# Electronic_Design_OpenBook_Hardware_v1.net
KiCad netlist of a schematic drawn in EAGLE
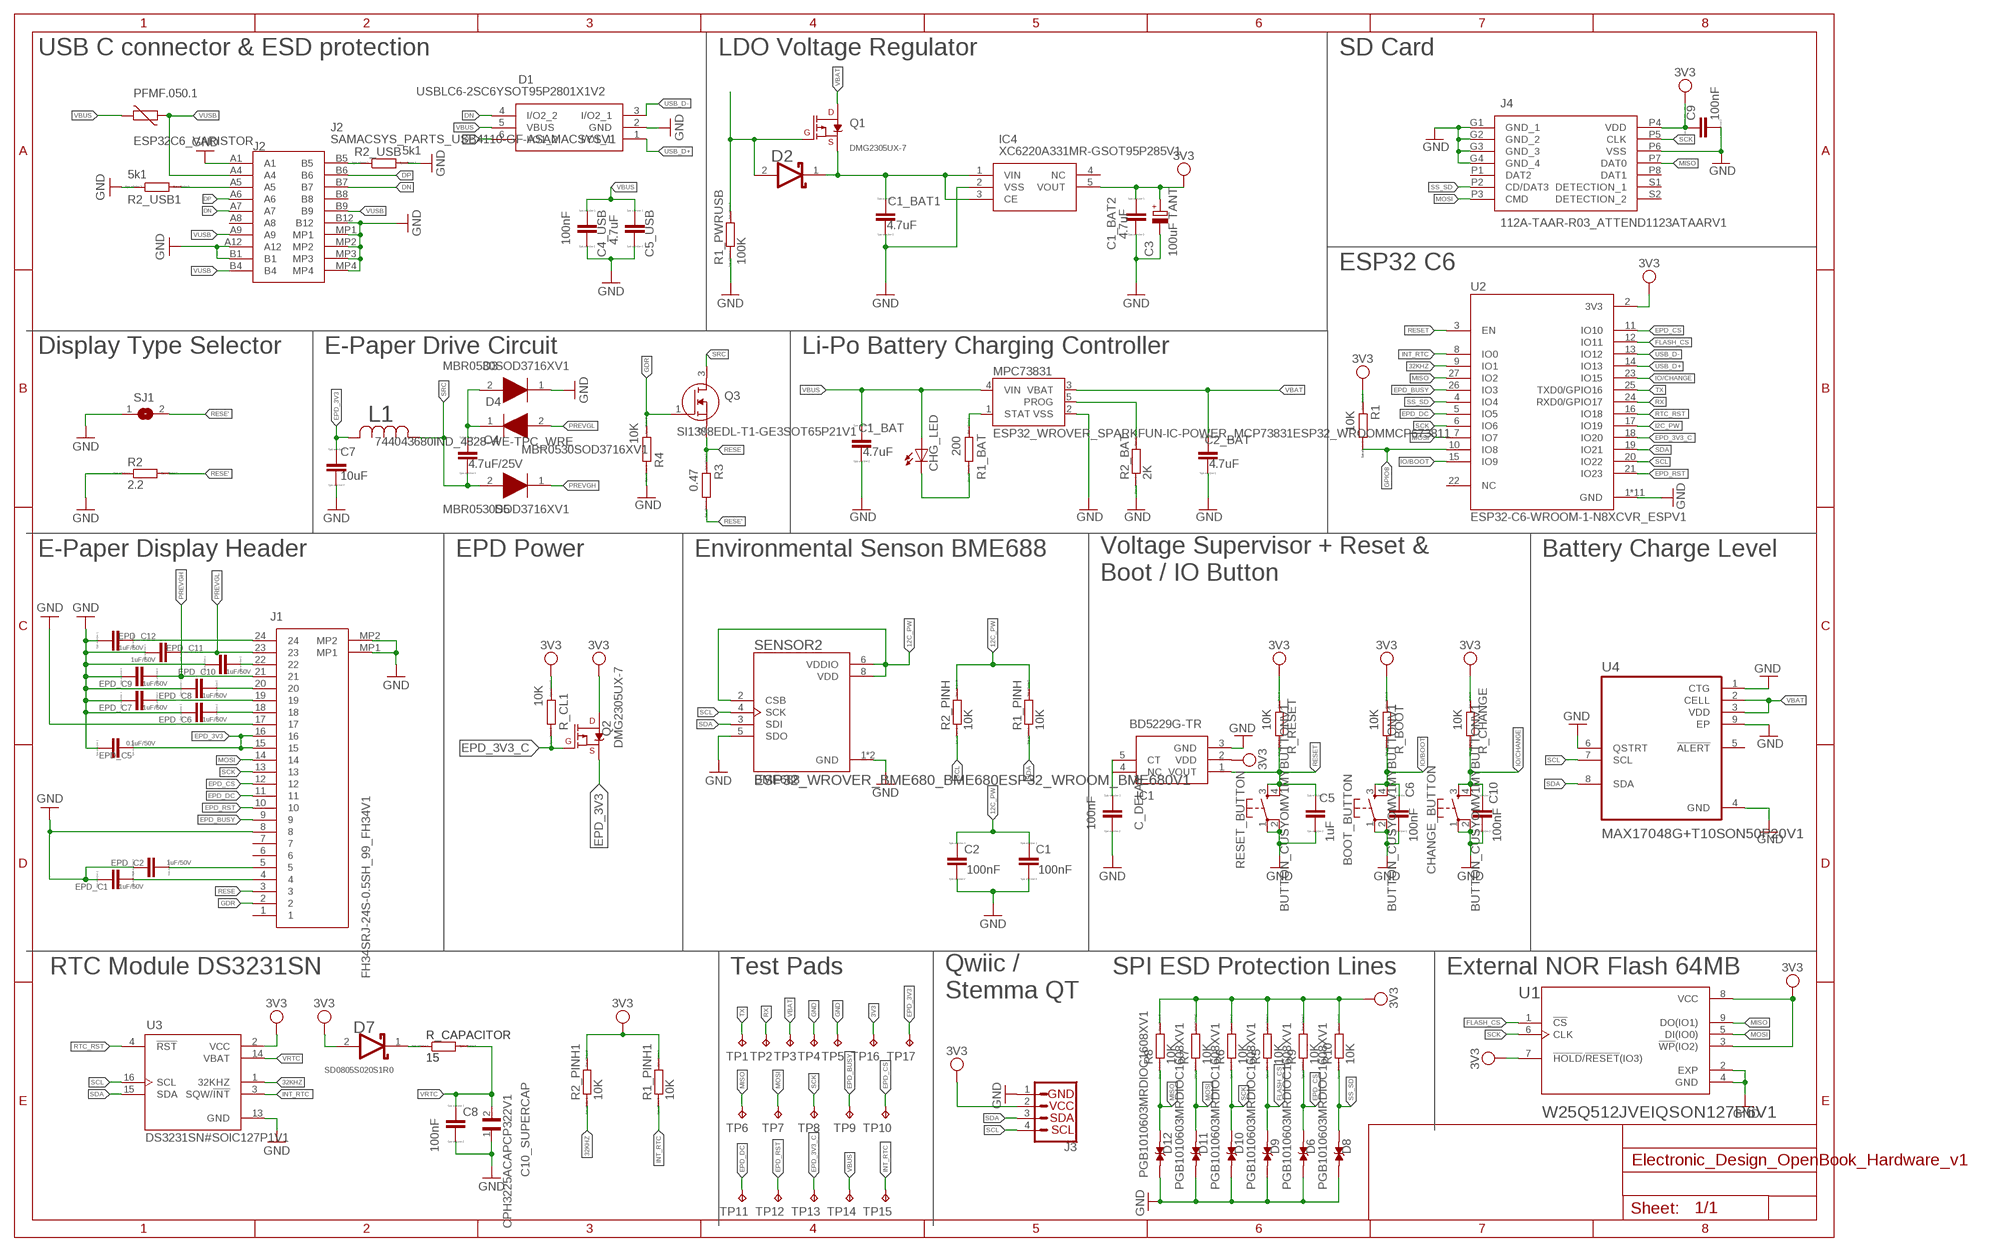
[diagram p0: schematic, sheet 1]

(export (version "E")
  (design (tool "Eeschema 10.0.6"))
  (components
    (comp (ref "BOOT_BUTTON")
      (value "BUTTON_CUSYOMV1MYBUTTONV1")
      (footprint "eagle-import:MYBUTTON")
      (libsource (lib "eagle-import") (part "BUTTON_CUSYOMV1MYBUTTONV1"))
    )
    (comp (ref "C1")
      (value "100nF")
      (footprint "eagle-import:EAGLE-LTSPICE_C0402")
      (libsource (lib "eagle-import") (part "EAGLE-LTSPICE_CC0402"))
    )
    (comp (ref "C1_BAT")
      (value "4.7uF")
      (footprint "eagle-import:ESP32_WROVER_EAGLE-LTSPICE_C0402")
      (libsource (lib "eagle-import") (part "ESP32_WROVER_EAGLE-LTSPICE_C"))
    )
    (comp (ref "C1_BAT1")
      (value "4.7uF")
      (footprint "eagle-import:ESP32_WROVER_EAGLE-LTSPICE_C0402")
      (libsource (lib "eagle-import") (part "ESP32_WROVER_EAGLE-LTSPICE_C"))
    )
    (comp (ref "C1_BAT2")
      (value "4.7uF")
      (footprint "eagle-import:ESP32_WROVER_EAGLE-LTSPICE_C0402")
      (libsource (lib "eagle-import") (part "ESP32_WROVER_EAGLE-LTSPICE_C"))
    )
    (comp (ref "C2")
      (value "100nF")
      (footprint "eagle-import:EAGLE-LTSPICE_C0402")
      (libsource (lib "eagle-import") (part "EAGLE-LTSPICE_CC0402"))
    )
    (comp (ref "C2_BAT")
      (value "4.7uF")
      (footprint "eagle-import:ESP32_WROVER_EAGLE-LTSPICE_C0402")
      (libsource (lib "eagle-import") (part "ESP32_WROVER_EAGLE-LTSPICE_C"))
    )
    (comp (ref "C3")
      (value "100uF TANT")
      (footprint "eagle-import:RCL_CT3528")
      (libsource (lib "eagle-import") (part "RCL_CPOL-EU"))
    )
    (comp (ref "C4")
      (value "4.7uF/25V")
      (footprint "eagle-import:ESP32_WROVER_EAGLE-LTSPICE_C0402")
      (libsource (lib "eagle-import") (part "ESP32_WROVER_EAGLE-LTSPICE_C"))
    )
    (comp (ref "C4_USB")
      (value "100nF")
      (footprint "eagle-import:ESP32_WROVER_EAGLE-LTSPICE_C0402")
      (libsource (lib "eagle-import") (part "ESP32_WROVER_EAGLE-LTSPICE_C"))
    )
    (comp (ref "C5")
      (value "1uF")
      (footprint "eagle-import:EAGLE-LTSPICE_C0402")
      (libsource (lib "eagle-import") (part "EAGLE-LTSPICE_CC0402"))
    )
    (comp (ref "C5_USB")
      (value "4.7uF")
      (footprint "eagle-import:ESP32_WROVER_EAGLE-LTSPICE_C0402")
      (libsource (lib "eagle-import") (part "ESP32_WROVER_EAGLE-LTSPICE_C"))
    )
    (comp (ref "C6")
      (value "100nF")
      (footprint "eagle-import:EAGLE-LTSPICE_C0402")
      (libsource (lib "eagle-import") (part "EAGLE-LTSPICE_CC0402"))
    )
    (comp (ref "C7")
      (value "10uF")
      (footprint "eagle-import:ESP32_WROVER_EAGLE-LTSPICE_C0402")
      (libsource (lib "eagle-import") (part "ESP32_WROVER_EAGLE-LTSPICE_C"))
    )
    (comp (ref "C8")
      (value "100nF")
      (footprint "eagle-import:EAGLE-LTSPICE_C0402")
      (libsource (lib "eagle-import") (part "EAGLE-LTSPICE_CC0402"))
    )
    (comp (ref "C9")
      (value "100nF")
      (footprint "eagle-import:ESP32_WROVER_EAGLE-LTSPICE_C0402")
      (libsource (lib "eagle-import") (part "ESP32_WROVER_EAGLE-LTSPICE_C"))
    )
    (comp (ref "C10")
      (value "100nF")
      (footprint "eagle-import:EAGLE-LTSPICE_C0402")
      (libsource (lib "eagle-import") (part "EAGLE-LTSPICE_CC0402"))
    )
    (comp (ref "C10_SUPERCAP")
      (value "CPH3225ACAPCP322V1")
      (footprint "eagle-import:CAPCP3225X100N")
      (libsource (lib "eagle-import") (part "CPH3225ACAPCP322V1"))
    )
    (comp (ref "CHANGE_BUTTON")
      (value "BUTTON_CUSYOMV1MYBUTTONV1")
      (footprint "eagle-import:MYBUTTON")
      (libsource (lib "eagle-import") (part "BUTTON_CUSYOMV1MYBUTTONV1"))
    )
    (comp (ref "CHG_LED")
      (value "ADAFRUIT_LED")
      (footprint "eagle-import:ADAFRUIT_CHIP-LED0603")
      (libsource (lib "eagle-import") (part "ADAFRUIT_LED"))
    )
    (comp (ref "C_DELAY")
      (value "100nF")
      (footprint "eagle-import:EAGLE-LTSPICE_C0402")
      (libsource (lib "eagle-import") (part "EAGLE-LTSPICE_CC0402"))
    )
    (comp (ref "D1")
      (value "USBLC6-2SC6YSOT95P2801X1V2")
      (footprint "eagle-import:SOT95P280X145-6N")
      (libsource (lib "eagle-import") (part "USBLC6-2SC6YSOT95P2801X1V2"))
    )
    (comp (ref "D2")
      (value "ESP32_WROVER_AVX---SD0805S020S1R0_AVX_SD0805S020S1R0_0_0")
      (footprint "eagle-import:ESP32_WROVER_AVX---SD0805S020S1R0_AVX_SD0805S020S1R0_0")
      (libsource (lib "eagle-import") (part "ESP32_WROVER_AVX---SD0805S020S1R0_AVX_SD0805S020S1R0_0_0"))
    )
    (comp (ref "D3")
      (value "MBR0530SOD3716XV1")
      (footprint "eagle-import:SOD3716X135N")
      (libsource (lib "eagle-import") (part "MBR0530SOD3716XV1"))
    )
    (comp (ref "D4")
      (value "MBR0530SOD3716XV1")
      (footprint "eagle-import:SOD3716X135N")
      (libsource (lib "eagle-import") (part "MBR0530SOD3716XV1"))
    )
    (comp (ref "D5")
      (value "MBR0530SOD3716XV1")
      (footprint "eagle-import:SOD3716X135N")
      (libsource (lib "eagle-import") (part "MBR0530SOD3716XV1"))
    )
    (comp (ref "D6")
      (value "PGB1010603MRDIOC1608XV1")
      (footprint "eagle-import:DIOC1608X36N")
      (libsource (lib "eagle-import") (part "PGB1010603MRDIOC1608XV1"))
    )
    (comp (ref "D7")
      (value "ESP32_WROVER_AVX---SD0805S020S1R0_AVX_SD0805S020S1R0_0_0")
      (footprint "eagle-import:ESP32_WROVER_AVX---SD0805S020S1R0_AVX_SD0805S020S1R0_0")
      (libsource (lib "eagle-import") (part "ESP32_WROVER_AVX---SD0805S020S1R0_AVX_SD0805S020S1R0_0_0"))
    )
    (comp (ref "D8")
      (value "PGB1010603MRDIOC1608XV1")
      (footprint "eagle-import:DIOC1608X36N")
      (libsource (lib "eagle-import") (part "PGB1010603MRDIOC1608XV1"))
    )
    (comp (ref "D9")
      (value "PGB1010603MRDIOC1608XV1")
      (footprint "eagle-import:DIOC1608X36N")
      (libsource (lib "eagle-import") (part "PGB1010603MRDIOC1608XV1"))
    )
    (comp (ref "D10")
      (value "PGB1010603MRDIOC1608XV1")
      (footprint "eagle-import:DIOC1608X36N")
      (libsource (lib "eagle-import") (part "PGB1010603MRDIOC1608XV1"))
    )
    (comp (ref "D11")
      (value "PGB1010603MRDIOC1608XV1")
      (footprint "eagle-import:DIOC1608X36N")
      (libsource (lib "eagle-import") (part "PGB1010603MRDIOC1608XV1"))
    )
    (comp (ref "D12")
      (value "PGB1010603MRDIOC1608XV1")
      (footprint "eagle-import:DIOC1608X36N")
      (libsource (lib "eagle-import") (part "PGB1010603MRDIOC1608XV1"))
    )
    (comp (ref "EPD_C1")
      (value "1uF/50V")
      (footprint "eagle-import:EAGLE-LTSPICE_C0402")
      (libsource (lib "eagle-import") (part "EAGLE-LTSPICE_CC0402"))
    )
    (comp (ref "EPD_C2")
      (value "1uF/50V")
      (footprint "eagle-import:EAGLE-LTSPICE_C0402")
      (libsource (lib "eagle-import") (part "EAGLE-LTSPICE_CC0402"))
    )
    (comp (ref "EPD_C5")
      (value "0.1uF/50V")
      (footprint "eagle-import:EAGLE-LTSPICE_C0402")
      (libsource (lib "eagle-import") (part "EAGLE-LTSPICE_CC0402"))
    )
    (comp (ref "EPD_C6")
      (value "1uF/50V")
      (footprint "eagle-import:EAGLE-LTSPICE_C0402")
      (libsource (lib "eagle-import") (part "EAGLE-LTSPICE_CC0402"))
    )
    (comp (ref "EPD_C7")
      (value "1uF/50V")
      (footprint "eagle-import:EAGLE-LTSPICE_C0402")
      (libsource (lib "eagle-import") (part "EAGLE-LTSPICE_CC0402"))
    )
    (comp (ref "EPD_C8")
      (value "1uF/50V")
      (footprint "eagle-import:EAGLE-LTSPICE_C0402")
      (libsource (lib "eagle-import") (part "EAGLE-LTSPICE_CC0402"))
    )
    (comp (ref "EPD_C9")
      (value "1uF/50V")
      (footprint "eagle-import:EAGLE-LTSPICE_C0402")
      (libsource (lib "eagle-import") (part "EAGLE-LTSPICE_CC0402"))
    )
    (comp (ref "EPD_C10")
      (value "1uF/50V")
      (footprint "eagle-import:EAGLE-LTSPICE_C0402")
      (libsource (lib "eagle-import") (part "EAGLE-LTSPICE_CC0402"))
    )
    (comp (ref "EPD_C11")
      (value "1uF/50V")
      (footprint "eagle-import:EAGLE-LTSPICE_C0402")
      (libsource (lib "eagle-import") (part "EAGLE-LTSPICE_CC0402"))
    )
    (comp (ref "EPD_C12")
      (value "1uF/50V")
      (footprint "eagle-import:EAGLE-LTSPICE_C0402")
      (libsource (lib "eagle-import") (part "EAGLE-LTSPICE_CC0402"))
    )
    (comp (ref "IC1")
      (value "BD5229G-TR")
      (footprint "eagle-import:SOT95P280X120-5N")
      (libsource (lib "eagle-import") (part "BD5229G-TR"))
    )
    (comp (ref "IC4")
      (value "XC6220A331MR-GSOT95P285V1")
      (footprint "eagle-import:SOT95P280X120-5N")
      (libsource (lib "eagle-import") (part "XC6220A331MR-GSOT95P285V1"))
    )
    (comp (ref "J1")
      (value "FH34SRJ-24S-0.5SH_99_FH34V1")
      (footprint "eagle-import:FH34SRJ24S05SH99")
      (libsource (lib "eagle-import") (part "FH34SRJ-24S-0.5SH_99_FH34V1"))
    )
    (comp (ref "J2")
      (value "SAMACSYS_PARTS_USB4110-GF-ASAMACSYSV1")
      (footprint "eagle-import:SAMACSYS_PARTS_USB4110GFA")
      (libsource (lib "eagle-import") (part "SAMACSYS_PARTS_USB4110-GF-ASAMACSYSV1"))
    )
    (comp (ref "J3")
      (value "QWIIC_RIGHT_ANGLE")
      (footprint "eagle-import:JST04_1MM_RA")
      (libsource (lib "eagle-import") (part "QWIIC_CONNECTOR"))
    )
    (comp (ref "J4")
      (value "112A-TAAR-R03_ATTEND1123ATAARV1")
      (footprint "eagle-import:112ATAARR03ATTEND")
      (libsource (lib "eagle-import") (part "112A-TAAR-R03_ATTEND1123ATAARV1"))
    )
    (comp (ref "L1")
      (value "744043680IND_4828-WE-TPC_WRE")
      (footprint "eagle-import:IND_4828-WE-TPC_WRE")
      (libsource (lib "eagle-import") (part "744043680"))
    )
    (comp (ref "MPC73831")
      (value "ESP32_WROVER_SPARKFUN-IC-POWER_MCP73831ESP32_WROOMMCP673811")
      (footprint "eagle-import:ESP32_WROVER_SPARKFUN-IC-POWER_SOT23-5")
      (libsource (lib "eagle-import") (part "ESP32_WROVER_SPARKFUN-IC-POWER_MCP73831ESP32_WROOMMCP673811"))
    )
    (comp (ref "PFMF.050.1")
      (value "ESP32C6_VARISTOR")
      (footprint "eagle-import:ESP32C6_VARISTOR_CT_CN1812")
      (libsource (lib "eagle-import") (part "ESP32C6_VARISTOR"))
    )
    (comp (ref "Q1")
      (value "20V/4.2A/52mΩ/1.4W")
      (footprint "eagle-import:ESP32_WROVER_SPARKFUN-DISCRETESEMI_SOT23-3")
      (libsource (lib "eagle-import") (part "ESP32_WROVER_SPARKFUN-DISCRETESEMI_MOSFET_PCH"))
    )
    (comp (ref "Q2")
      (value "20V/4.2A/52mΩ/1.4W")
      (footprint "eagle-import:ESP32_WROVER_SPARKFUN-DISCRETESEMI_SOT23-3")
      (libsource (lib "eagle-import") (part "ESP32_WROVER_SPARKFUN-DISCRETESEMI_MOSFET_PCH"))
    )
    (comp (ref "Q3")
      (value "SI1308EDL-T1-GE3SOT65P21V1")
      (footprint "eagle-import:SOT65P210X110-3N")
      (libsource (lib "eagle-import") (part "SI1308EDL-T1-GE3SOT65P21V1"))
    )
    (comp (ref "R1")
      (value "10K")
      (footprint "eagle-import:ESP32_WROVER_EAGLE-LTSPICE_R0402")
      (libsource (lib "eagle-import") (part "ESP32_WROVER_EAGLE-LTSPICE_R"))
    )
    (comp (ref "R1_BAT")
      (value "200")
      (footprint "eagle-import:ESP32_WROVER_EAGLE-LTSPICE_R0402")
      (libsource (lib "eagle-import") (part "ESP32_WROVER_EAGLE-LTSPICE_R"))
    )
    (comp (ref "R1_PINH")
      (value "10K")
      (footprint "eagle-import:ESP32_WROVER_EAGLE-LTSPICE_R0402")
      (libsource (lib "eagle-import") (part "ESP32_WROVER_EAGLE-LTSPICE_R"))
    )
    (comp (ref "R1_PINH1")
      (value "10K")
      (footprint "eagle-import:ESP32_WROVER_EAGLE-LTSPICE_R0402")
      (libsource (lib "eagle-import") (part "ESP32_WROVER_EAGLE-LTSPICE_R"))
    )
    (comp (ref "R1_PWRUSB")
      (value "100K")
      (footprint "eagle-import:ESP32_WROVER_EAGLE-LTSPICE_R0402")
      (libsource (lib "eagle-import") (part "ESP32_WROVER_EAGLE-LTSPICE_R"))
    )
    (comp (ref "R2")
      (value "2.2")
      (footprint "eagle-import:ESP32_WROVER_EAGLE-LTSPICE_R0402")
      (libsource (lib "eagle-import") (part "ESP32_WROVER_EAGLE-LTSPICE_R"))
    )
    (comp (ref "R2_BAT")
      (value "2K")
      (footprint "eagle-import:ESP32_WROVER_EAGLE-LTSPICE_R0402")
      (libsource (lib "eagle-import") (part "ESP32_WROVER_EAGLE-LTSPICE_R"))
    )
    (comp (ref "R2_PINH")
      (value "10K")
      (footprint "eagle-import:ESP32_WROVER_EAGLE-LTSPICE_R0402")
      (libsource (lib "eagle-import") (part "ESP32_WROVER_EAGLE-LTSPICE_R"))
    )
    (comp (ref "R2_PINH1")
      (value "10K")
      (footprint "eagle-import:ESP32_WROVER_EAGLE-LTSPICE_R0402")
      (libsource (lib "eagle-import") (part "ESP32_WROVER_EAGLE-LTSPICE_R"))
    )
    (comp (ref "R2_USB")
      (value "5k1")
      (footprint "eagle-import:ESP32_WROVER_EAGLE-LTSPICE_R0402")
      (libsource (lib "eagle-import") (part "ESP32_WROVER_EAGLE-LTSPICE_R"))
    )
    (comp (ref "R2_USB1")
      (value "5k1")
      (footprint "eagle-import:ESP32_WROVER_EAGLE-LTSPICE_R0402")
      (libsource (lib "eagle-import") (part "ESP32_WROVER_EAGLE-LTSPICE_R"))
    )
    (comp (ref "R3")
      (value "0.47")
      (footprint "eagle-import:ESP32_WROVER_EAGLE-LTSPICE_R0402")
      (libsource (lib "eagle-import") (part "ESP32_WROVER_EAGLE-LTSPICE_R"))
    )
    (comp (ref "R4")
      (value "10K")
      (footprint "eagle-import:ESP32_WROVER_EAGLE-LTSPICE_R0402")
      (libsource (lib "eagle-import") (part "ESP32_WROVER_EAGLE-LTSPICE_R"))
    )
    (comp (ref "R5")
      (value "10K")
      (footprint "eagle-import:ESP32_WROVER_EAGLE-LTSPICE_R0402")
      (libsource (lib "eagle-import") (part "ESP32_WROVER_EAGLE-LTSPICE_R"))
    )
    (comp (ref "R6")
      (value "10K")
      (footprint "eagle-import:ESP32_WROVER_EAGLE-LTSPICE_R0402")
      (libsource (lib "eagle-import") (part "ESP32_WROVER_EAGLE-LTSPICE_R"))
    )
    (comp (ref "R7")
      (value "10K")
      (footprint "eagle-import:ESP32_WROVER_EAGLE-LTSPICE_R0402")
      (libsource (lib "eagle-import") (part "ESP32_WROVER_EAGLE-LTSPICE_R"))
    )
    (comp (ref "R8")
      (value "10K")
      (footprint "eagle-import:ESP32_WROVER_EAGLE-LTSPICE_R0402")
      (libsource (lib "eagle-import") (part "ESP32_WROVER_EAGLE-LTSPICE_R"))
    )
    (comp (ref "R9")
      (value "10K")
      (footprint "eagle-import:ESP32_WROVER_EAGLE-LTSPICE_R0402")
      (libsource (lib "eagle-import") (part "ESP32_WROVER_EAGLE-LTSPICE_R"))
    )
    (comp (ref "R10")
      (value "10K")
      (footprint "eagle-import:ESP32_WROVER_EAGLE-LTSPICE_R0402")
      (libsource (lib "eagle-import") (part "ESP32_WROVER_EAGLE-LTSPICE_R"))
    )
    (comp (ref "RESET_BUTTON")
      (value "BUTTON_CUSYOMV1MYBUTTONV1")
      (footprint "eagle-import:MYBUTTON")
      (libsource (lib "eagle-import") (part "BUTTON_CUSYOMV1MYBUTTONV1"))
    )
    (comp (ref "R_BOOT")
      (value "10K")
      (footprint "eagle-import:ESP32_WROVER_EAGLE-LTSPICE_R0402")
      (libsource (lib "eagle-import") (part "ESP32_WROVER_EAGLE-LTSPICE_R"))
    )
    (comp (ref "R_CAPACITOR")
      (value "15")
      (footprint "eagle-import:ESP32_WROVER_EAGLE-LTSPICE_R0402")
      (libsource (lib "eagle-import") (part "ESP32_WROVER_EAGLE-LTSPICE_R"))
    )
    (comp (ref "R_CHANGE")
      (value "10K")
      (footprint "eagle-import:ESP32_WROVER_EAGLE-LTSPICE_R0402")
      (libsource (lib "eagle-import") (part "ESP32_WROVER_EAGLE-LTSPICE_R"))
    )
    (comp (ref "R_CL1")
      (value "10K")
      (footprint "eagle-import:ESP32_WROVER_EAGLE-LTSPICE_R0402")
      (libsource (lib "eagle-import") (part "ESP32_WROVER_EAGLE-LTSPICE_R"))
    )
    (comp (ref "R_RESET")
      (value "10K")
      (footprint "eagle-import:ESP32_WROVER_EAGLE-LTSPICE_R0402")
      (libsource (lib "eagle-import") (part "ESP32_WROVER_EAGLE-LTSPICE_R"))
    )
    (comp (ref "SENSOR2")
      (value "ESP32_WROVER_BME680_BME680ESP32_WROOM_BME680V1")
      (footprint "eagle-import:ESP32_WROVER_BME680_PSON80P300X300X100-8N")
      (libsource (lib "eagle-import") (part "ESP32_WROVER_BME680_BME680ESP32_WROOM_BME680V1"))
    )
    (comp (ref "SJ1")
      (value "SJSJV1")
      (footprint "eagle-import:SJ")
      (libsource (lib "eagle-import") (part "SJSJV1"))
    )
    (comp (ref "TP1")
      (value "TPTP20R")
      (footprint "eagle-import:TP20R")
      (libsource (lib "eagle-import") (part "TPTP20R"))
    )
    (comp (ref "TP2")
      (value "TPTP20R")
      (footprint "eagle-import:TP20R")
      (libsource (lib "eagle-import") (part "TPTP20R"))
    )
    (comp (ref "TP3")
      (value "TPTP20R")
      (footprint "eagle-import:TP20R")
      (libsource (lib "eagle-import") (part "TPTP20R"))
    )
    (comp (ref "TP4")
      (value "TPTP20R")
      (footprint "eagle-import:TP20R")
      (libsource (lib "eagle-import") (part "TPTP20R"))
    )
    (comp (ref "TP5")
      (value "TPTP20R")
      (footprint "eagle-import:TP20R")
      (libsource (lib "eagle-import") (part "TPTP20R"))
    )
    (comp (ref "TP6")
      (value "TPTP20R")
      (footprint "eagle-import:TP20R")
      (libsource (lib "eagle-import") (part "TPTP20R"))
    )
    (comp (ref "TP7")
      (value "TPTP20R")
      (footprint "eagle-import:TP20R")
      (libsource (lib "eagle-import") (part "TPTP20R"))
    )
    (comp (ref "TP8")
      (value "TPTP20R")
      (footprint "eagle-import:TP20R")
      (libsource (lib "eagle-import") (part "TPTP20R"))
    )
    (comp (ref "TP9")
      (value "TPTP20R")
      (footprint "eagle-import:TP20R")
      (libsource (lib "eagle-import") (part "TPTP20R"))
    )
    (comp (ref "TP10")
      (value "TPTP20R")
      (footprint "eagle-import:TP20R")
      (libsource (lib "eagle-import") (part "TPTP20R"))
    )
    (comp (ref "TP11")
      (value "TPTP20R")
      (footprint "eagle-import:TP20R")
      (libsource (lib "eagle-import") (part "TPTP20R"))
    )
    (comp (ref "TP12")
      (value "TPTP20R")
      (footprint "eagle-import:TP20R")
      (libsource (lib "eagle-import") (part "TPTP20R"))
    )
    (comp (ref "TP13")
      (value "TPTP20R")
      (footprint "eagle-import:TP20R")
      (libsource (lib "eagle-import") (part "TPTP20R"))
    )
    (comp (ref "TP14")
      (value "TPTP20R")
      (footprint "eagle-import:TP20R")
      (libsource (lib "eagle-import") (part "TPTP20R"))
    )
    (comp (ref "TP15")
      (value "TPTP20R")
      (footprint "eagle-import:TP20R")
      (libsource (lib "eagle-import") (part "TPTP20R"))
    )
    (comp (ref "TP16")
      (value "TPTP20R")
      (footprint "eagle-import:TP20R")
      (libsource (lib "eagle-import") (part "TPTP20R"))
    )
    (comp (ref "TP17")
      (value "TPTP20R")
      (footprint "eagle-import:TP20R")
      (libsource (lib "eagle-import") (part "TPTP20R"))
    )
    (comp (ref "U1")
      (value "W25Q512JVEIQSON127P6V1")
      (footprint "eagle-import:SON127P600X800X80-9N")
      (libsource (lib "eagle-import") (part "W25Q512JVEIQSON127P6V1"))
    )
    (comp (ref "U2")
      (value "ESP32-C6-WROOM-1-N8XCVR_ESPV1")
      (footprint "eagle-import:XCVR_ESP32-C6-WROOM-1-N8")
      (libsource (lib "eagle-import") (part "ESP32-C6-WROOM-1-N8XCVR_ESPV1"))
    )
    (comp (ref "U3")
      (value "DS3231SN#SOIC127P1V1")
      (footprint "eagle-import:SOIC127P1032X265-16N")
      (libsource (lib "eagle-import") (part "DS3231SN#SOIC127P1V1"))
    )
    (comp (ref "U4")
      (value "MAX17048G+T10SON50P20V1")
      (footprint "eagle-import:SON50P200X200X80-9N")
      (libsource (lib "eagle-import") (part "MAX17048G+T10SON50P20V1"))
    )
  )
  (nets
    (net (code "1") (name "3V3") (class "Default")
      (node (ref "C1_BAT2") (pin "1") (pinfunction "1_1") (pintype "passive"))
      (node (ref "C3") (pin "+") (pinfunction "+_+") (pintype "passive"))
      (node (ref "C9") (pin "1") (pinfunction "1_1") (pintype "passive"))
      (node (ref "D7") (pin "2") (pinfunction "ANODE_2") (pintype "bidirectional"))
      (node (ref "IC1") (pin "2") (pinfunction "VDD_2") (pintype "bidirectional"))
      (node (ref "IC4") (pin "5") (pinfunction "VOUT_5") (pintype "bidirectional"))
      (node (ref "J3") (pin "2") (pinfunction "2_2") (pintype "power_in"))
      (node (ref "J4") (pin "P4") (pinfunction "VDD_P4") (pintype "bidirectional"))
      (node (ref "Q2") (pin "3") (pinfunction "D_3") (pintype "bidirectional"))
      (node (ref "R1") (pin "2") (pinfunction "2_2") (pintype "passive"))
      (node (ref "R10") (pin "2") (pinfunction "2_2") (pintype "passive"))
      (node (ref "R1_PINH1") (pin "2") (pinfunction "2_2") (pintype "passive"))
      (node (ref "R2_PINH1") (pin "2") (pinfunction "2_2") (pintype "passive"))
      (node (ref "R5") (pin "2") (pinfunction "2_2") (pintype "passive"))
      (node (ref "R6") (pin "2") (pinfunction "2_2") (pintype "passive"))
      (node (ref "R7") (pin "2") (pinfunction "2_2") (pintype "passive"))
      (node (ref "R8") (pin "2") (pinfunction "2_2") (pintype "passive"))
      (node (ref "R9") (pin "2") (pinfunction "2_2") (pintype "passive"))
      (node (ref "R_BOOT") (pin "2") (pinfunction "2_2") (pintype "passive"))
      (node (ref "R_CHANGE") (pin "2") (pinfunction "2_2") (pintype "passive"))
      (node (ref "R_CL1") (pin "2") (pinfunction "2_2") (pintype "passive"))
      (node (ref "R_RESET") (pin "2") (pinfunction "2_2") (pintype "passive"))
      (node (ref "TP16") (pin "TP") (pinfunction "TP_TP") (pintype "input"))
      (node (ref "U1") (pin "3") (pinfunction "~{WP}(IO2)_3") (pintype "bidirectional"))
      (node (ref "U1") (pin "7") (pinfunction "~{HOLD}/~{RESET}(IO3)_7") (pintype "bidirectional"))
      (node (ref "U1") (pin "8") (pinfunction "VCC_8") (pintype "power_in"))
      (node (ref "U2") (pin "2") (pinfunction "3V3_2") (pintype "power_in"))
      (node (ref "U3") (pin "2") (pinfunction "VCC_2") (pintype "power_in"))
    )
    (net (code "2") (name "12C_PW") (class "Default")
      (node (ref "C1") (pin "1") (pinfunction "1_1") (pintype "passive"))
      (node (ref "C2") (pin "1") (pinfunction "1_1") (pintype "passive"))
      (node (ref "R1_PINH") (pin "2") (pinfunction "2_2") (pintype "passive"))
      (node (ref "R2_PINH") (pin "2") (pinfunction "2_2") (pintype "passive"))
      (node (ref "SENSOR2") (pin "2") (pinfunction "CSB_2") (pintype "input"))
      (node (ref "SENSOR2") (pin "6") (pinfunction "VDDIO_6") (pintype "power_in"))
      (node (ref "SENSOR2") (pin "8") (pinfunction "VDD_8") (pintype "power_in"))
    )
    (net (code "3") (name "32KHZ") (class "Default")
      (node (ref "R2_PINH1") (pin "1") (pinfunction "1_1") (pintype "passive"))
      (node (ref "U2") (pin "9") (pinfunction "IO1_9") (pintype "bidirectional"))
      (node (ref "U3") (pin "1") (pinfunction "32KHZ_1") (pintype "output"))
    )
    (net (code "4") (name "DN") (class "Default")
      (node (ref "D1") (pin "4") (pinfunction "I/O2_2_4") (pintype "bidirectional"))
      (node (ref "J2") (pin "A7") (pinfunction "A7_A7") (pintype "bidirectional"))
      (node (ref "J2") (pin "B7") (pinfunction "B7_B7") (pintype "bidirectional"))
    )
    (net (code "5") (name "DP") (class "Default")
      (node (ref "D1") (pin "6") (pinfunction "I/O1_2_6") (pintype "bidirectional"))
      (node (ref "J2") (pin "A6") (pinfunction "A6_A6") (pintype "bidirectional"))
      (node (ref "J2") (pin "B6") (pinfunction "B6_B6") (pintype "bidirectional"))
    )
    (net (code "6") (name "EPD_3V3") (class "Default")
      (node (ref "C7") (pin "1") (pinfunction "1_1") (pintype "passive"))
      (node (ref "EPD_C5") (pin "2") (pinfunction "2_2") (pintype "passive"))
      (node (ref "J1") (pin "15") (pinfunction "15_15") (pintype "bidirectional"))
      (node (ref "J1") (pin "16") (pinfunction "16_16") (pintype "bidirectional"))
      (node (ref "L1") (pin "2") (pinfunction "2_2") (pintype "passive"))
      (node (ref "Q2") (pin "2") (pinfunction "S_2") (pintype "bidirectional"))
      (node (ref "TP17") (pin "TP") (pinfunction "TP_TP") (pintype "input"))
    )
    (net (code "7") (name "EPD_3V3_C") (class "Default")
      (node (ref "Q2") (pin "1") (pinfunction "G_1") (pintype "bidirectional"))
      (node (ref "R_CL1") (pin "1") (pinfunction "1_1") (pintype "passive"))
      (node (ref "TP13") (pin "TP") (pinfunction "TP_TP") (pintype "input"))
      (node (ref "U2") (pin "18") (pinfunction "IO20_18") (pintype "bidirectional"))
    )
    (net (code "8") (name "EPD_BUSY") (class "Default")
      (node (ref "J1") (pin "9") (pinfunction "9_9") (pintype "bidirectional"))
      (node (ref "TP9") (pin "TP") (pinfunction "TP_TP") (pintype "input"))
      (node (ref "U2") (pin "26") (pinfunction "IO3_26") (pintype "bidirectional"))
    )
    (net (code "9") (name "EPD_CS") (class "Default")
      (node (ref "D6") (pin "2") (pinfunction "2_2") (pintype "passive"))
      (node (ref "J1") (pin "12") (pinfunction "12_12") (pintype "bidirectional"))
      (node (ref "R9") (pin "1") (pinfunction "1_1") (pintype "passive"))
      (node (ref "TP10") (pin "TP") (pinfunction "TP_TP") (pintype "input"))
      (node (ref "U2") (pin "11") (pinfunction "IO10_11") (pintype "bidirectional"))
    )
    (net (code "10") (name "EPD_DC") (class "Default")
      (node (ref "J1") (pin "11") (pinfunction "11_11") (pintype "bidirectional"))
      (node (ref "TP11") (pin "TP") (pinfunction "TP_TP") (pintype "input"))
      (node (ref "U2") (pin "5") (pinfunction "IO5_5") (pintype "bidirectional"))
    )
    (net (code "11") (name "EPD_RST") (class "Default")
      (node (ref "J1") (pin "10") (pinfunction "10_10") (pintype "bidirectional"))
      (node (ref "TP12") (pin "TP") (pinfunction "TP_TP") (pintype "input"))
      (node (ref "U2") (pin "21") (pinfunction "IO23_21") (pintype "bidirectional"))
    )
    (net (code "12") (name "FLASH_CS") (class "Default")
      (node (ref "D9") (pin "2") (pinfunction "2_2") (pintype "passive"))
      (node (ref "R5") (pin "1") (pinfunction "1_1") (pintype "passive"))
      (node (ref "U1") (pin "1") (pinfunction "~{CS}_1") (pintype "input"))
      (node (ref "U2") (pin "12") (pinfunction "IO11_12") (pintype "bidirectional"))
    )
    (net (code "13") (name "GDR") (class "Default")
      (node (ref "J1") (pin "2") (pinfunction "2_2") (pintype "bidirectional"))
      (node (ref "Q3") (pin "1") (pinfunction "G_1") (pintype "bidirectional"))
      (node (ref "R4") (pin "2") (pinfunction "2_2") (pintype "passive"))
    )
    (net (code "14") (name "GND") (class "Default")
      (node (ref "BOOT_BUTTON") (pin "1") (pinfunction "1_1") (pintype "passive"))
      (node (ref "BOOT_BUTTON") (pin "2") (pinfunction "2_2") (pintype "passive"))
      (node (ref "C1") (pin "2") (pinfunction "2_2") (pintype "passive"))
      (node (ref "C10") (pin "2") (pinfunction "2_2") (pintype "passive"))
      (node (ref "C10_SUPERCAP") (pin "1") (pinfunction "1_1") (pintype "passive"))
      (node (ref "C1_BAT") (pin "2") (pinfunction "2_2") (pintype "passive"))
      (node (ref "C1_BAT1") (pin "2") (pinfunction "2_2") (pintype "passive"))
      (node (ref "C1_BAT2") (pin "2") (pinfunction "2_2") (pintype "passive"))
      (node (ref "C2") (pin "2") (pinfunction "2_2") (pintype "passive"))
      (node (ref "C2_BAT") (pin "2") (pinfunction "2_2") (pintype "passive"))
      (node (ref "C3") (pin "-") (pinfunction "-_-") (pintype "passive"))
      (node (ref "C4_USB") (pin "2") (pinfunction "2_2") (pintype "passive"))
      (node (ref "C5") (pin "2") (pinfunction "2_2") (pintype "passive"))
      (node (ref "C5_USB") (pin "2") (pinfunction "2_2") (pintype "passive"))
      (node (ref "C6") (pin "2") (pinfunction "2_2") (pintype "passive"))
      (node (ref "C7") (pin "2") (pinfunction "2_2") (pintype "passive"))
      (node (ref "C8") (pin "2") (pinfunction "2_2") (pintype "passive"))
      (node (ref "C9") (pin "2") (pinfunction "2_2") (pintype "passive"))
      (node (ref "CHANGE_BUTTON") (pin "1") (pinfunction "1_1") (pintype "passive"))
      (node (ref "CHANGE_BUTTON") (pin "2") (pinfunction "2_2") (pintype "passive"))
      (node (ref "C_DELAY") (pin "2") (pinfunction "2_2") (pintype "passive"))
      (node (ref "D1") (pin "2") (pinfunction "GND_2") (pintype "bidirectional"))
      (node (ref "D10") (pin "1") (pinfunction "1_1") (pintype "passive"))
      (node (ref "D11") (pin "1") (pinfunction "1_1") (pintype "passive"))
      (node (ref "D12") (pin "1") (pinfunction "1_1") (pintype "passive"))
      (node (ref "D3") (pin "1") (pinfunction "K_1") (pintype "bidirectional"))
      (node (ref "D6") (pin "1") (pinfunction "1_1") (pintype "passive"))
      (node (ref "D8") (pin "1") (pinfunction "1_1") (pintype "passive"))
      (node (ref "D9") (pin "1") (pinfunction "1_1") (pintype "passive"))
      (node (ref "EPD_C1") (pin "1") (pinfunction "1_1") (pintype "passive"))
      (node (ref "EPD_C10") (pin "1") (pinfunction "1_1") (pintype "passive"))
      (node (ref "EPD_C11") (pin "1") (pinfunction "1_1") (pintype "passive"))
      (node (ref "EPD_C12") (pin "1") (pinfunction "1_1") (pintype "passive"))
      (node (ref "EPD_C2") (pin "1") (pinfunction "1_1") (pintype "passive"))
      (node (ref "EPD_C5") (pin "1") (pinfunction "1_1") (pintype "passive"))
      (node (ref "EPD_C6") (pin "1") (pinfunction "1_1") (pintype "passive"))
      (node (ref "EPD_C7") (pin "1") (pinfunction "1_1") (pintype "passive"))
      (node (ref "EPD_C8") (pin "1") (pinfunction "1_1") (pintype "passive"))
      (node (ref "EPD_C9") (pin "1") (pinfunction "1_1") (pintype "passive"))
      (node (ref "IC1") (pin "3") (pinfunction "GND_3") (pintype "bidirectional"))
      (node (ref "IC4") (pin "2") (pinfunction "VSS_2") (pintype "bidirectional"))
      (node (ref "J1") (pin "17") (pinfunction "17_17") (pintype "bidirectional"))
      (node (ref "J1") (pin "8") (pinfunction "8_8") (pintype "bidirectional"))
      (node (ref "J1") (pin "MP1") (pinfunction "MP1_MP1") (pintype "bidirectional"))
      (node (ref "J1") (pin "MP2") (pinfunction "MP2_MP2") (pintype "bidirectional"))
      (node (ref "J2") (pin "A1") (pinfunction "A1_A1") (pintype "bidirectional"))
      (node (ref "J2") (pin "A12") (pinfunction "A12_A12") (pintype "bidirectional"))
      (node (ref "J2") (pin "B1") (pinfunction "B1_B1") (pintype "bidirectional"))
      (node (ref "J2") (pin "B12") (pinfunction "B12_B12") (pintype "bidirectional"))
      (node (ref "J2") (pin "MP1") (pinfunction "MP1_MP1") (pintype "bidirectional"))
      (node (ref "J2") (pin "MP2") (pinfunction "MP2_MP2") (pintype "bidirectional"))
      (node (ref "J2") (pin "MP3") (pinfunction "MP3_MP3") (pintype "bidirectional"))
      (node (ref "J2") (pin "MP4") (pinfunction "MP4_MP4") (pintype "bidirectional"))
      (node (ref "J3") (pin "1") (pinfunction "1_1") (pintype "power_in"))
      (node (ref "J4") (pin "G1") (pinfunction "GND_1_G1") (pintype "bidirectional"))
      (node (ref "J4") (pin "G2") (pinfunction "GND_2_G2") (pintype "bidirectional"))
      (node (ref "J4") (pin "G3") (pinfunction "GND_3_G3") (pintype "bidirectional"))
      (node (ref "J4") (pin "G4") (pinfunction "GND_4_G4") (pintype "bidirectional"))
      (node (ref "J4") (pin "P6") (pinfunction "VSS_P6") (pintype "bidirectional"))
      (node (ref "MPC73831") (pin "2") (pinfunction "VSS_2") (pintype "power_in"))
      (node (ref "R1_PWRUSB") (pin "1") (pinfunction "1_1") (pintype "passive"))
      (node (ref "R2") (pin "1") (pinfunction "1_1") (pintype "passive"))
      (node (ref "R2_BAT") (pin "1") (pinfunction "1_1") (pintype "passive"))
      (node (ref "R2_USB") (pin "2") (pinfunction "2_2") (pintype "passive"))
      (node (ref "R2_USB1") (pin "1") (pinfunction "1_1") (pintype "passive"))
      (node (ref "R4") (pin "1") (pinfunction "1_1") (pintype "passive"))
      (node (ref "RESET_BUTTON") (pin "1") (pinfunction "1_1") (pintype "passive"))
      (node (ref "RESET_BUTTON") (pin "2") (pinfunction "2_2") (pintype "passive"))
      (node (ref "SENSOR2") (pin "1") (pinfunction "GND_1") (pintype "power_in"))
      (node (ref "SENSOR2") (pin "5") (pinfunction "SDO_5") (pintype "bidirectional"))
      (node (ref "SENSOR2") (pin "7") (pinfunction "GND_7") (pintype "power_in"))
      (node (ref "SJ1") (pin "1") (pinfunction "1_1") (pintype "passive"))
      (node (ref "TP4") (pin "TP") (pinfunction "TP_TP") (pintype "input"))
      (node (ref "TP5") (pin "TP") (pinfunction "TP_TP") (pintype "input"))
      (node (ref "U1") (pin "2") (pinfunction "EXP_2") (pintype "passive"))
      (node (ref "U1") (pin "4") (pinfunction "GND_4") (pintype "power_in"))
      (node (ref "U2") (pin "1") (pinfunction "GND_1") (pintype "power_in"))
      (node (ref "U2") (pin "28") (pinfunction "GND_28") (pintype "power_in"))
      (node (ref "U2") (pin "29_1") (pinfunction "GND_29_1") (pintype "power_in"))
      (node (ref "U2") (pin "29_2") (pinfunction "GND_29_2") (pintype "power_in"))
      (node (ref "U2") (pin "29_3") (pinfunction "GND_29_3") (pintype "power_in"))
      (node (ref "U2") (pin "29_4") (pinfunction "GND_29_4") (pintype "power_in"))
      (node (ref "U2") (pin "29_5") (pinfunction "GND_29_5") (pintype "power_in"))
      (node (ref "U2") (pin "29_6") (pinfunction "GND_29_6") (pintype "power_in"))
      (node (ref "U2") (pin "29_7") (pinfunction "GND_29_7") (pintype "power_in"))
      (node (ref "U2") (pin "29_8") (pinfunction "GND_29_8") (pintype "power_in"))
      (node (ref "U2") (pin "29_9") (pinfunction "GND_29_9") (pintype "power_in"))
      (node (ref "U3") (pin "13") (pinfunction "GND_13") (pintype "power_in"))
      (node (ref "U4") (pin "1") (pinfunction "CTG_1") (pintype "power_in"))
      (node (ref "U4") (pin "4") (pinfunction "GND_4") (pintype "power_in"))
      (node (ref "U4") (pin "6") (pinfunction "QSTRT_6") (pintype "input"))
      (node (ref "U4") (pin "9") (pinfunction "EP_9") (pintype "power_in"))
    )
    (net (code "15") (name "GPIO8") (class "Default")
      (node (ref "R1") (pin "1") (pinfunction "1_1") (pintype "passive"))
      (node (ref "U2") (pin "10") (pinfunction "IO8_10") (pintype "bidirectional"))
    )
    (net (code "16") (name "I2C_PW") (class "Default")
      (node (ref "U2") (pin "17") (pinfunction "IO19_17") (pintype "bidirectional"))
    )
    (net (code "17") (name "INT_RTC") (class "Default")
      (node (ref "R1_PINH1") (pin "1") (pinfunction "1_1") (pintype "passive"))
      (node (ref "TP15") (pin "TP") (pinfunction "TP_TP") (pintype "input"))
      (node (ref "U2") (pin "8") (pinfunction "IO0_8") (pintype "bidirectional"))
      (node (ref "U3") (pin "3") (pinfunction "SQW/~{INT}_3") (pintype "output"))
    )
    (net (code "18") (name "IO{slash}BOOT") (class "Default")
      (node (ref "BOOT_BUTTON") (pin "3") (pinfunction "3_3") (pintype "passive"))
      (node (ref "BOOT_BUTTON") (pin "4") (pinfunction "4_4") (pintype "passive"))
      (node (ref "C6") (pin "1") (pinfunction "1_1") (pintype "passive"))
      (node (ref "R_BOOT") (pin "1") (pinfunction "1_1") (pintype "passive"))
      (node (ref "U2") (pin "15") (pinfunction "IO9_15") (pintype "bidirectional"))
    )
    (net (code "19") (name "IO{slash}CHANGE") (class "Default")
      (node (ref "C10") (pin "1") (pinfunction "1_1") (pintype "passive"))
      (node (ref "CHANGE_BUTTON") (pin "3") (pinfunction "3_3") (pintype "passive"))
      (node (ref "CHANGE_BUTTON") (pin "4") (pinfunction "4_4") (pintype "passive"))
      (node (ref "R_CHANGE") (pin "1") (pinfunction "1_1") (pintype "passive"))
      (node (ref "U2") (pin "23") (pinfunction "IO15_23") (pintype "bidirectional"))
    )
    (net (code "20") (name "MISO") (class "Default")
      (node (ref "D12") (pin "2") (pinfunction "2_2") (pintype "passive"))
      (node (ref "J4") (pin "P7") (pinfunction "DAT0_P7") (pintype "bidirectional"))
      (node (ref "R8") (pin "1") (pinfunction "1_1") (pintype "passive"))
      (node (ref "TP6") (pin "TP") (pinfunction "TP_TP") (pintype "input"))
      (node (ref "U1") (pin "9") (pinfunction "DO(IO1)_9") (pintype "bidirectional"))
      (node (ref "U2") (pin "27") (pinfunction "IO2_27") (pintype "bidirectional"))
    )
    (net (code "21") (name "MOSI") (class "Default")
      (node (ref "D11") (pin "2") (pinfunction "2_2") (pintype "passive"))
      (node (ref "J1") (pin "14") (pinfunction "14_14") (pintype "bidirectional"))
      (node (ref "J4") (pin "P3") (pinfunction "CMD_P3") (pintype "bidirectional"))
      (node (ref "R7") (pin "1") (pinfunction "1_1") (pintype "passive"))
      (node (ref "TP7") (pin "TP") (pinfunction "TP_TP") (pintype "input"))
      (node (ref "U1") (pin "5") (pinfunction "DI(IO0)_5") (pintype "bidirectional"))
      (node (ref "U2") (pin "7") (pinfunction "IO7_7") (pintype "bidirectional"))
    )
    (net (code "22") (name "Net-(CHG_LED-PadC)") (class "Default")
      (node (ref "CHG_LED") (pin "C") (pinfunction "C_C") (pintype "passive"))
      (node (ref "R1_BAT") (pin "1") (pinfunction "1_1") (pintype "passive"))
    )
    (net (code "23") (name "Net-(D2-ANODE)") (class "Default")
      (node (ref "D2") (pin "2") (pinfunction "ANODE_2") (pintype "bidirectional"))
      (node (ref "Q1") (pin "1") (pinfunction "G_1") (pintype "bidirectional"))
      (node (ref "R1_PWRUSB") (pin "2") (pinfunction "2_2") (pintype "passive"))
    )
    (net (code "24") (name "Net-(D2-CATHODE)") (class "Default")
      (node (ref "C1_BAT1") (pin "1") (pinfunction "1_1") (pintype "passive"))
      (node (ref "D2") (pin "1") (pinfunction "CATHODE_1") (pintype "bidirectional"))
      (node (ref "IC4") (pin "1") (pinfunction "VIN_1") (pintype "bidirectional"))
      (node (ref "IC4") (pin "3") (pinfunction "CE_3") (pintype "bidirectional"))
      (node (ref "Q1") (pin "2") (pinfunction "S_2") (pintype "bidirectional"))
    )
    (net (code "25") (name "Net-(D3-A)") (class "Default")
      (node (ref "C4") (pin "1") (pinfunction "1_1") (pintype "passive"))
      (node (ref "D3") (pin "2") (pinfunction "A_2") (pintype "bidirectional"))
      (node (ref "D4") (pin "1") (pinfunction "K_1") (pintype "bidirectional"))
    )
    (net (code "26") (name "Net-(D7-CATHODE)") (class "Default")
      (node (ref "D7") (pin "1") (pinfunction "CATHODE_1") (pintype "bidirectional"))
      (node (ref "R_CAPACITOR") (pin "1") (pinfunction "1_1") (pintype "passive"))
    )
    (net (code "27") (name "Net-(EPD_C1-Pad2)") (class "Default")
      (node (ref "EPD_C1") (pin "2") (pinfunction "2_2") (pintype "passive"))
      (node (ref "J1") (pin "4") (pinfunction "4_4") (pintype "bidirectional"))
    )
    (net (code "28") (name "Net-(EPD_C2-Pad2)") (class "Default")
      (node (ref "EPD_C2") (pin "2") (pinfunction "2_2") (pintype "passive"))
      (node (ref "J1") (pin "5") (pinfunction "5_5") (pintype "bidirectional"))
    )
    (net (code "29") (name "Net-(EPD_C6-Pad2)") (class "Default")
      (node (ref "EPD_C6") (pin "2") (pinfunction "2_2") (pintype "passive"))
      (node (ref "J1") (pin "18") (pinfunction "18_18") (pintype "bidirectional"))
    )
    (net (code "30") (name "Net-(EPD_C7-Pad2)") (class "Default")
      (node (ref "EPD_C7") (pin "2") (pinfunction "2_2") (pintype "passive"))
      (node (ref "J1") (pin "19") (pinfunction "19_19") (pintype "bidirectional"))
    )
    (net (code "31") (name "Net-(EPD_C8-Pad2)") (class "Default")
      (node (ref "EPD_C8") (pin "2") (pinfunction "2_2") (pintype "passive"))
      (node (ref "J1") (pin "20") (pinfunction "20_20") (pintype "bidirectional"))
    )
    (net (code "32") (name "Net-(EPD_C10-Pad2)") (class "Default")
      (node (ref "EPD_C10") (pin "2") (pinfunction "2_2") (pintype "passive"))
      (node (ref "J1") (pin "22") (pinfunction "22_22") (pintype "bidirectional"))
    )
    (net (code "33") (name "Net-(EPD_C12-Pad2)") (class "Default")
      (node (ref "EPD_C12") (pin "2") (pinfunction "2_2") (pintype "passive"))
      (node (ref "J1") (pin "24") (pinfunction "24_24") (pintype "bidirectional"))
    )
    (net (code "34") (name "Net-(IC1-CT)") (class "Default")
      (node (ref "C_DELAY") (pin "1") (pinfunction "1_1") (pintype "passive"))
      (node (ref "IC1") (pin "5") (pinfunction "CT_5") (pintype "bidirectional"))
    )
    (net (code "35") (name "Net-(J2-PadA5)") (class "Default")
      (node (ref "J2") (pin "A5") (pinfunction "A5_A5") (pintype "bidirectional"))
      (node (ref "R2_USB1") (pin "2") (pinfunction "2_2") (pintype "passive"))
    )
    (net (code "36") (name "Net-(J2-PadB5)") (class "Default")
      (node (ref "J2") (pin "B5") (pinfunction "B5_B5") (pintype "bidirectional"))
      (node (ref "R2_USB") (pin "1") (pinfunction "1_1") (pintype "passive"))
    )
    (net (code "37") (name "Net-(MPC73831-PROG)") (class "Default")
      (node (ref "MPC73831") (pin "5") (pinfunction "PROG_5") (pintype "input"))
      (node (ref "R2_BAT") (pin "2") (pinfunction "2_2") (pintype "passive"))
    )
    (net (code "38") (name "Net-(MPC73831-STAT)") (class "Default")
      (node (ref "MPC73831") (pin "1") (pinfunction "STAT_1") (pintype "output"))
      (node (ref "R1_BAT") (pin "2") (pinfunction "2_2") (pintype "passive"))
    )
    (net (code "39") (name "PREVGH") (class "Default")
      (node (ref "D5") (pin "1") (pinfunction "K_1") (pintype "bidirectional"))
      (node (ref "EPD_C9") (pin "2") (pinfunction "2_2") (pintype "passive"))
      (node (ref "J1") (pin "21") (pinfunction "21_21") (pintype "bidirectional"))
    )
    (net (code "40") (name "PREVGL") (class "Default")
      (node (ref "D4") (pin "2") (pinfunction "A_2") (pintype "bidirectional"))
      (node (ref "EPD_C11") (pin "2") (pinfunction "2_2") (pintype "passive"))
      (node (ref "J1") (pin "23") (pinfunction "23_23") (pintype "bidirectional"))
    )
    (net (code "41") (name "RESE") (class "Default")
      (node (ref "J1") (pin "3") (pinfunction "3_3") (pintype "bidirectional"))
      (node (ref "Q3") (pin "2") (pinfunction "S_2") (pintype "bidirectional"))
      (node (ref "R3") (pin "2") (pinfunction "2_2") (pintype "passive"))
    )
    (net (code "42") (name "RESE'") (class "Default")
      (node (ref "R2") (pin "2") (pinfunction "2_2") (pintype "passive"))
      (node (ref "R3") (pin "1") (pinfunction "1_1") (pintype "passive"))
      (node (ref "SJ1") (pin "2") (pinfunction "2_2") (pintype "passive"))
    )
    (net (code "43") (name "RESET") (class "Default")
      (node (ref "C5") (pin "1") (pinfunction "1_1") (pintype "passive"))
      (node (ref "IC1") (pin "1") (pinfunction "VOUT_1") (pintype "bidirectional"))
      (node (ref "RESET_BUTTON") (pin "3") (pinfunction "3_3") (pintype "passive"))
      (node (ref "RESET_BUTTON") (pin "4") (pinfunction "4_4") (pintype "passive"))
      (node (ref "R_RESET") (pin "1") (pinfunction "1_1") (pintype "passive"))
      (node (ref "U2") (pin "3") (pinfunction "EN_3") (pintype "input"))
    )
    (net (code "44") (name "RTC_RST") (class "Default")
      (node (ref "U2") (pin "16") (pinfunction "IO18_16") (pintype "bidirectional"))
      (node (ref "U3") (pin "4") (pinfunction "~{RST}_4") (pintype "input"))
    )
    (net (code "45") (name "RX") (class "Default")
      (node (ref "TP2") (pin "TP") (pinfunction "TP_TP") (pintype "input"))
      (node (ref "U2") (pin "24") (pinfunction "RXD0/GPIO17_24") (pintype "bidirectional"))
    )
    (net (code "46") (name "SCK") (class "Default")
      (node (ref "D10") (pin "2") (pinfunction "2_2") (pintype "passive"))
      (node (ref "J1") (pin "13") (pinfunction "13_13") (pintype "bidirectional"))
      (node (ref "J4") (pin "P5") (pinfunction "CLK_P5") (pintype "bidirectional"))
      (node (ref "R6") (pin "1") (pinfunction "1_1") (pintype "passive"))
      (node (ref "TP8") (pin "TP") (pinfunction "TP_TP") (pintype "input"))
      (node (ref "U1") (pin "6") (pinfunction "CLK_6") (pintype "input"))
      (node (ref "U2") (pin "6") (pinfunction "IO6_6") (pintype "bidirectional"))
    )
    (net (code "47") (name "SCL") (class "Default")
      (node (ref "J3") (pin "4") (pinfunction "4_4") (pintype "passive"))
      (node (ref "R2_PINH") (pin "1") (pinfunction "1_1") (pintype "passive"))
      (node (ref "SENSOR2") (pin "4") (pinfunction "SCK_4") (pintype "input"))
      (node (ref "U2") (pin "20") (pinfunction "IO22_20") (pintype "bidirectional"))
      (node (ref "U3") (pin "16") (pinfunction "SCL_16") (pintype "input"))
      (node (ref "U4") (pin "7") (pinfunction "SCL_7") (pintype "input"))
    )
    (net (code "48") (name "SDA") (class "Default")
      (node (ref "J3") (pin "3") (pinfunction "3_3") (pintype "passive"))
      (node (ref "R1_PINH") (pin "1") (pinfunction "1_1") (pintype "passive"))
      (node (ref "SENSOR2") (pin "3") (pinfunction "SDI_3") (pintype "bidirectional"))
      (node (ref "U2") (pin "19") (pinfunction "IO21_19") (pintype "bidirectional"))
      (node (ref "U3") (pin "15") (pinfunction "SDA_15") (pintype "bidirectional"))
      (node (ref "U4") (pin "8") (pinfunction "SDA_8") (pintype "bidirectional"))
    )
    (net (code "49") (name "SRC") (class "Default")
      (node (ref "C4") (pin "2") (pinfunction "2_2") (pintype "passive"))
      (node (ref "D5") (pin "2") (pinfunction "A_2") (pintype "bidirectional"))
      (node (ref "L1") (pin "1") (pinfunction "1_1") (pintype "passive"))
      (node (ref "Q3") (pin "3") (pinfunction "D_3") (pintype "bidirectional"))
    )
    (net (code "50") (name "SS_SD") (class "Default")
      (node (ref "D8") (pin "2") (pinfunction "2_2") (pintype "passive"))
      (node (ref "J4") (pin "P2") (pinfunction "CD/DAT3_P2") (pintype "bidirectional"))
      (node (ref "R10") (pin "1") (pinfunction "1_1") (pintype "passive"))
      (node (ref "U2") (pin "4") (pinfunction "IO4_4") (pintype "bidirectional"))
    )
    (net (code "51") (name "TX") (class "Default")
      (node (ref "TP1") (pin "TP") (pinfunction "TP_TP") (pintype "input"))
      (node (ref "U2") (pin "25") (pinfunction "TXD0/GPIO16_25") (pintype "bidirectional"))
    )
    (net (code "52") (name "USB_D+") (class "Default")
      (node (ref "D1") (pin "1") (pinfunction "I/O1_1_1") (pintype "bidirectional"))
      (node (ref "U2") (pin "14") (pinfunction "IO13_14") (pintype "bidirectional"))
    )
    (net (code "53") (name "USB_D-") (class "Default")
      (node (ref "D1") (pin "3") (pinfunction "I/O2_1_3") (pintype "bidirectional"))
      (node (ref "U2") (pin "13") (pinfunction "IO12_13") (pintype "bidirectional"))
    )
    (net (code "54") (name "VBAT") (class "Default")
      (node (ref "C2_BAT") (pin "1") (pinfunction "1_1") (pintype "passive"))
      (node (ref "MPC73831") (pin "3") (pinfunction "VBAT_3") (pintype "power_in"))
      (node (ref "Q1") (pin "3") (pinfunction "D_3") (pintype "bidirectional"))
      (node (ref "TP3") (pin "TP") (pinfunction "TP_TP") (pintype "input"))
      (node (ref "U4") (pin "2") (pinfunction "CELL_2") (pintype "power_in"))
      (node (ref "U4") (pin "3") (pinfunction "VDD_3") (pintype "power_in"))
    )
    (net (code "55") (name "VBUS") (class "Default")
      (node (ref "C1_BAT") (pin "1") (pinfunction "1_1") (pintype "passive"))
      (node (ref "C4_USB") (pin "1") (pinfunction "1_1") (pintype "passive"))
      (node (ref "C5_USB") (pin "1") (pinfunction "1_1") (pintype "passive"))
      (node (ref "CHG_LED") (pin "A") (pinfunction "A_A") (pintype "passive"))
      (node (ref "D1") (pin "5") (pinfunction "VBUS_5") (pintype "bidirectional"))
      (node (ref "MPC73831") (pin "4") (pinfunction "VIN_4") (pintype "power_in"))
      (node (ref "PFMF.050.1") (pin "2") (pinfunction "2_2") (pintype "passive"))
      (node (ref "TP14") (pin "TP") (pinfunction "TP_TP") (pintype "input"))
    )
    (net (code "56") (name "VRTC") (class "Default")
      (node (ref "C10_SUPERCAP") (pin "2") (pinfunction "2_2") (pintype "passive"))
      (node (ref "C8") (pin "1") (pinfunction "1_1") (pintype "passive"))
      (node (ref "R_CAPACITOR") (pin "2") (pinfunction "2_2") (pintype "passive"))
      (node (ref "U3") (pin "14") (pinfunction "VBAT_14") (pintype "power_in"))
    )
    (net (code "57") (name "VUSB") (class "Default")
      (node (ref "J2") (pin "A4") (pinfunction "A4_A4") (pintype "bidirectional"))
      (node (ref "J2") (pin "A9") (pinfunction "A9_A9") (pintype "bidirectional"))
      (node (ref "J2") (pin "B4") (pinfunction "B4_B4") (pintype "bidirectional"))
      (node (ref "J2") (pin "B9") (pinfunction "B9_B9") (pintype "bidirectional"))
      (node (ref "PFMF.050.1") (pin "1") (pinfunction "1_1") (pintype "passive"))
    )
    (net (code "58") (name "unconnected-(IC1-NC-Pad4)") (class "Default")
      (node (ref "IC1") (pin "4") (pinfunction "NC_4") (pintype "no_connect"))
    )
    (net (code "59") (name "unconnected-(IC4-NC-Pad4)") (class "Default")
      (node (ref "IC4") (pin "4") (pinfunction "NC_4") (pintype "no_connect"))
    )
    (net (code "60") (name "unconnected-(J1-Pad1)") (class "Default")
      (node (ref "J1") (pin "1") (pinfunction "1_1") (pintype "bidirectional"))
    )
    (net (code "61") (name "unconnected-(J1-Pad6)") (class "Default")
      (node (ref "J1") (pin "6") (pinfunction "6_6") (pintype "bidirectional"))
    )
    (net (code "62") (name "unconnected-(J1-Pad7)") (class "Default")
      (node (ref "J1") (pin "7") (pinfunction "7_7") (pintype "bidirectional"))
    )
    (net (code "63") (name "unconnected-(J2-PadA8)") (class "Default")
      (node (ref "J2") (pin "A8") (pinfunction "A8_A8") (pintype "bidirectional"))
    )
    (net (code "64") (name "unconnected-(J2-PadB8)") (class "Default")
      (node (ref "J2") (pin "B8") (pinfunction "B8_B8") (pintype "bidirectional"))
    )
    (net (code "65") (name "unconnected-(J4-DAT1-PadP8)") (class "Default")
      (node (ref "J4") (pin "P8") (pinfunction "DAT1_P8") (pintype "bidirectional"))
    )
    (net (code "66") (name "unconnected-(J4-DAT2-PadP1)") (class "Default")
      (node (ref "J4") (pin "P1") (pinfunction "DAT2_P1") (pintype "bidirectional"))
    )
    (net (code "67") (name "unconnected-(J4-DETECTION_1-PadS1)") (class "Default")
      (node (ref "J4") (pin "S1") (pinfunction "DETECTION_1_S1") (pintype "bidirectional"))
    )
    (net (code "68") (name "unconnected-(J4-DETECTION_2-PadS2)") (class "Default")
      (node (ref "J4") (pin "S2") (pinfunction "DETECTION_2_S2") (pintype "bidirectional"))
    )
    (net (code "69") (name "unconnected-(U2-NC-Pad22)") (class "Default")
      (node (ref "U2") (pin "22") (pinfunction "NC_22") (pintype "no_connect"))
    )
    (net (code "70") (name "unconnected-(U4-~{ALERT}-Pad5)") (class "Default")
      (node (ref "U4") (pin "5") (pinfunction "~{ALERT}_5") (pintype "output"))
    )
  )
)
